# LED_MAT_HUB.net
KiCad netlist of a schematic drawn in Altium Designer
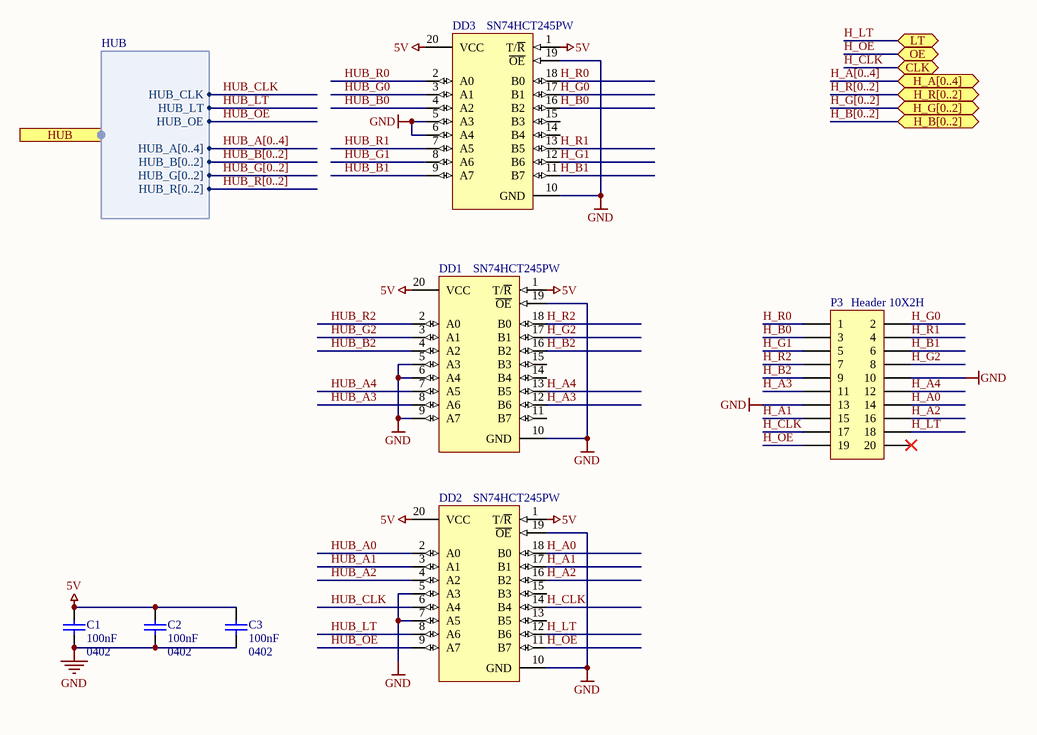
[diagram p0: LED_MAT_HUB.SchDoc]

(export (version "E")
  (design (tool "Eeschema 10.0.6"))
  (components
    (comp (ref "C1")
      (value "100nF")
      (footprint "CAPC1005L")
      (description "Capacitor ceramic")
      (fields
        (field (name "MANUFACTURER") "SAMSUNG")
        (field (name "MANUFACTURER PART NUMBER") "CL05B104KO5NNNC")
        (field (name "PACKAGE") "0402")
      )
      (libsource (lib "LED_MAT_3") (part "100nF / 0402 / X7R / 16V"))
    )
    (comp (ref "C2")
      (value "100nF")
      (footprint "CAPC1005L")
      (description "Capacitor ceramic")
      (fields
        (field (name "MANUFACTURER") "SAMSUNG")
        (field (name "MANUFACTURER PART NUMBER") "CL05B104KO5NNNC")
        (field (name "PACKAGE") "0402")
      )
      (libsource (lib "LED_MAT_3") (part "100nF / 0402 / X7R / 16V"))
    )
    (comp (ref "C3")
      (value "100nF")
      (footprint "CAPC1005L")
      (description "Capacitor ceramic")
      (fields
        (field (name "MANUFACTURER") "SAMSUNG")
        (field (name "MANUFACTURER PART NUMBER") "CL05B104KO5NNNC")
        (field (name "PACKAGE") "0402")
      )
      (libsource (lib "LED_MAT_3") (part "100nF / 0402 / X7R / 16V"))
    )
    (comp (ref "DD1")
      (value "SN74HCT245PW")
      (footprint "PW020_N")
      (description "Octal 3-State Noninverting Bus Transceiver")
      (fields
        (field (name "MANUFACTURER") "NEXPERIA")
        (field (name "MANUFACTURER PART NUMBER") "SN74HCT245PW")
      )
      (libsource (lib "LED_MAT_3") (part "SN74HCT245PW"))
    )
    (comp (ref "DD2")
      (value "SN74HCT245PW")
      (footprint "PW020_N")
      (description "Octal 3-State Noninverting Bus Transceiver")
      (fields
        (field (name "MANUFACTURER") "NEXPERIA")
        (field (name "MANUFACTURER PART NUMBER") "SN74HCT245PW")
      )
      (libsource (lib "LED_MAT_3") (part "SN74HCT245PW"))
    )
    (comp (ref "DD3")
      (value "SN74HCT245PW")
      (footprint "PW020_N")
      (description "Octal 3-State Noninverting Bus Transceiver")
      (fields
        (field (name "MANUFACTURER") "NEXPERIA")
        (field (name "MANUFACTURER PART NUMBER") "SN74HCT245PW")
      )
      (libsource (lib "LED_MAT_3") (part "SN74HCT245PW"))
    )
    (comp (ref "P3")
      (value "Header 10X2H")
      (footprint "HDR2X10H")
      (description "Header, 10-Pin, Dual row, Right Angle")
      (libsource (lib "LED_MAT_3") (part "Header 10X2H"))
    )
  )
  (nets
    (net (code "2") (name "/HUB_A0") (class "Default")
      (node (ref "DD2") (pin "2") (pinfunction "A0_2") (pintype "bidirectional"))
    )
    (net (code "3") (name "/HUB_A1") (class "Default")
      (node (ref "DD2") (pin "3") (pinfunction "A1_3") (pintype "bidirectional"))
    )
    (net (code "4") (name "/HUB_A2") (class "Default")
      (node (ref "DD2") (pin "4") (pinfunction "A2_4") (pintype "bidirectional"))
    )
    (net (code "5") (name "/HUB_A3") (class "Default")
      (node (ref "DD1") (pin "8") (pinfunction "A6_8") (pintype "bidirectional"))
    )
    (net (code "6") (name "/HUB_A4") (class "Default")
      (node (ref "DD1") (pin "7") (pinfunction "A5_7") (pintype "bidirectional"))
    )
    (net (code "7") (name "/HUB_B0") (class "Default")
      (node (ref "DD3") (pin "4") (pinfunction "A2_4") (pintype "bidirectional"))
    )
    (net (code "8") (name "/HUB_B1") (class "Default")
      (node (ref "DD3") (pin "9") (pinfunction "A7_9") (pintype "bidirectional"))
    )
    (net (code "9") (name "/HUB_B2") (class "Default")
      (node (ref "DD1") (pin "4") (pinfunction "A2_4") (pintype "bidirectional"))
    )
    (net (code "11") (name "/HUB_CLK") (class "Default")
      (node (ref "DD2") (pin "6") (pinfunction "A4_6") (pintype "bidirectional"))
    )
    (net (code "12") (name "/HUB_G0") (class "Default")
      (node (ref "DD3") (pin "3") (pinfunction "A1_3") (pintype "bidirectional"))
    )
    (net (code "13") (name "/HUB_G1") (class "Default")
      (node (ref "DD3") (pin "8") (pinfunction "A6_8") (pintype "bidirectional"))
    )
    (net (code "14") (name "/HUB_G2") (class "Default")
      (node (ref "DD1") (pin "3") (pinfunction "A1_3") (pintype "bidirectional"))
    )
    (net (code "16") (name "/HUB_LT") (class "Default")
      (node (ref "DD2") (pin "8") (pinfunction "A6_8") (pintype "bidirectional"))
    )
    (net (code "17") (name "/HUB_OE") (class "Default")
      (node (ref "DD2") (pin "9") (pinfunction "A7_9") (pintype "bidirectional"))
    )
    (net (code "18") (name "/HUB_R0") (class "Default")
      (node (ref "DD3") (pin "2") (pinfunction "A0_2") (pintype "bidirectional"))
    )
    (net (code "19") (name "/HUB_R1") (class "Default")
      (node (ref "DD3") (pin "7") (pinfunction "A5_7") (pintype "bidirectional"))
    )
    (net (code "20") (name "/HUB_R2") (class "Default")
      (node (ref "DD1") (pin "2") (pinfunction "A0_2") (pintype "bidirectional"))
    )
    (net (code "23") (name "/H_A0") (class "Default")
      (node (ref "DD2") (pin "18") (pinfunction "B0_18") (pintype "bidirectional"))
      (node (ref "P3") (pin "14") (pinfunction "14_14") (pintype "passive"))
    )
    (net (code "24") (name "/H_A1") (class "Default")
      (node (ref "DD2") (pin "17") (pinfunction "B1_17") (pintype "bidirectional"))
      (node (ref "P3") (pin "15") (pinfunction "15_15") (pintype "passive"))
    )
    (net (code "25") (name "/H_A2") (class "Default")
      (node (ref "DD2") (pin "16") (pinfunction "B2_16") (pintype "bidirectional"))
      (node (ref "P3") (pin "16") (pinfunction "16_16") (pintype "passive"))
    )
    (net (code "26") (name "/H_A3") (class "Default")
      (node (ref "DD1") (pin "12") (pinfunction "B6_12") (pintype "bidirectional"))
      (node (ref "P3") (pin "11") (pinfunction "11_11") (pintype "passive"))
    )
    (net (code "27") (name "/H_A4") (class "Default")
      (node (ref "DD1") (pin "13") (pinfunction "B5_13") (pintype "bidirectional"))
      (node (ref "P3") (pin "12") (pinfunction "12_12") (pintype "passive"))
    )
    (net (code "29") (name "/H_B0") (class "Default")
      (node (ref "DD3") (pin "16") (pinfunction "B2_16") (pintype "bidirectional"))
      (node (ref "P3") (pin "3") (pinfunction "3_3") (pintype "passive"))
    )
    (net (code "30") (name "/H_B1") (class "Default")
      (node (ref "DD3") (pin "11") (pinfunction "B7_11") (pintype "bidirectional"))
      (node (ref "P3") (pin "6") (pinfunction "6_6") (pintype "passive"))
    )
    (net (code "31") (name "/H_B2") (class "Default")
      (node (ref "DD1") (pin "16") (pinfunction "B2_16") (pintype "bidirectional"))
      (node (ref "P3") (pin "9") (pinfunction "9_9") (pintype "passive"))
    )
    (net (code "33") (name "/H_CLK") (class "Default")
      (node (ref "DD2") (pin "14") (pinfunction "B4_14") (pintype "bidirectional"))
      (node (ref "P3") (pin "17") (pinfunction "17_17") (pintype "passive"))
    )
    (net (code "34") (name "/H_G0") (class "Default")
      (node (ref "DD3") (pin "17") (pinfunction "B1_17") (pintype "bidirectional"))
      (node (ref "P3") (pin "2") (pinfunction "2_2") (pintype "passive"))
    )
    (net (code "35") (name "/H_G1") (class "Default")
      (node (ref "DD3") (pin "12") (pinfunction "B6_12") (pintype "bidirectional"))
      (node (ref "P3") (pin "5") (pinfunction "5_5") (pintype "passive"))
    )
    (net (code "36") (name "/H_G2") (class "Default")
      (node (ref "DD1") (pin "17") (pinfunction "B1_17") (pintype "bidirectional"))
      (node (ref "P3") (pin "8") (pinfunction "8_8") (pintype "passive"))
    )
    (net (code "38") (name "/H_LT") (class "Default")
      (node (ref "DD2") (pin "12") (pinfunction "B6_12") (pintype "bidirectional"))
      (node (ref "P3") (pin "18") (pinfunction "18_18") (pintype "passive"))
    )
    (net (code "39") (name "/H_OE") (class "Default")
      (node (ref "DD2") (pin "11") (pinfunction "B7_11") (pintype "bidirectional"))
      (node (ref "P3") (pin "19") (pinfunction "19_19") (pintype "passive"))
    )
    (net (code "40") (name "/H_R0") (class "Default")
      (node (ref "DD3") (pin "18") (pinfunction "B0_18") (pintype "bidirectional"))
      (node (ref "P3") (pin "1") (pinfunction "1_1") (pintype "passive"))
    )
    (net (code "41") (name "/H_R1") (class "Default")
      (node (ref "DD3") (pin "13") (pinfunction "B5_13") (pintype "bidirectional"))
      (node (ref "P3") (pin "4") (pinfunction "4_4") (pintype "passive"))
    )
    (net (code "42") (name "/H_R2") (class "Default")
      (node (ref "DD1") (pin "18") (pinfunction "B0_18") (pintype "bidirectional"))
      (node (ref "P3") (pin "7") (pinfunction "7_7") (pintype "passive"))
    )
    (net (code "44") (name "5V") (class "Default")
      (node (ref "C1") (pin "2") (pinfunction "2_2") (pintype "passive"))
      (node (ref "C2") (pin "2") (pinfunction "2_2") (pintype "passive"))
      (node (ref "C3") (pin "2") (pinfunction "2_2") (pintype "passive"))
      (node (ref "DD1") (pin "1") (pinfunction "T/~{R}_1") (pintype "input"))
      (node (ref "DD1") (pin "20") (pinfunction "VCC_20") (pintype "power_in"))
      (node (ref "DD2") (pin "1") (pinfunction "T/~{R}_1") (pintype "input"))
      (node (ref "DD2") (pin "20") (pinfunction "VCC_20") (pintype "power_in"))
      (node (ref "DD3") (pin "1") (pinfunction "T/~{R}_1") (pintype "input"))
      (node (ref "DD3") (pin "20") (pinfunction "VCC_20") (pintype "power_in"))
    )
    (net (code "45") (name "GND") (class "Default")
      (node (ref "C1") (pin "1") (pinfunction "1_1") (pintype "passive"))
      (node (ref "C2") (pin "1") (pinfunction "1_1") (pintype "passive"))
      (node (ref "C3") (pin "1") (pinfunction "1_1") (pintype "passive"))
      (node (ref "DD1") (pin "10") (pinfunction "GND_10") (pintype "power_in"))
      (node (ref "DD1") (pin "19") (pinfunction "~{OE}_19") (pintype "input"))
      (node (ref "DD1") (pin "5") (pinfunction "A3_5") (pintype "bidirectional"))
      (node (ref "DD1") (pin "6") (pinfunction "A4_6") (pintype "bidirectional"))
      (node (ref "DD1") (pin "9") (pinfunction "A7_9") (pintype "bidirectional"))
      (node (ref "DD2") (pin "10") (pinfunction "GND_10") (pintype "power_in"))
      (node (ref "DD2") (pin "19") (pinfunction "~{OE}_19") (pintype "input"))
      (node (ref "DD2") (pin "5") (pinfunction "A3_5") (pintype "bidirectional"))
      (node (ref "DD2") (pin "7") (pinfunction "A5_7") (pintype "bidirectional"))
      (node (ref "DD3") (pin "10") (pinfunction "GND_10") (pintype "power_in"))
      (node (ref "DD3") (pin "19") (pinfunction "~{OE}_19") (pintype "input"))
      (node (ref "DD3") (pin "5") (pinfunction "A3_5") (pintype "bidirectional"))
      (node (ref "DD3") (pin "6") (pinfunction "A4_6") (pintype "bidirectional"))
      (node (ref "P3") (pin "10") (pinfunction "10_10") (pintype "passive"))
      (node (ref "P3") (pin "13") (pinfunction "13_13") (pintype "passive"))
    )
    (net (code "46") (name "unconnected-(DD1-B3-Pad15)") (class "Default")
      (node (ref "DD1") (pin "15") (pinfunction "B3_15") (pintype "bidirectional"))
    )
    (net (code "47") (name "unconnected-(DD1-B4-Pad14)") (class "Default")
      (node (ref "DD1") (pin "14") (pinfunction "B4_14") (pintype "bidirectional"))
    )
    (net (code "48") (name "unconnected-(DD1-B7-Pad11)") (class "Default")
      (node (ref "DD1") (pin "11") (pinfunction "B7_11") (pintype "bidirectional"))
    )
    (net (code "49") (name "unconnected-(DD2-B3-Pad15)") (class "Default")
      (node (ref "DD2") (pin "15") (pinfunction "B3_15") (pintype "bidirectional"))
    )
    (net (code "50") (name "unconnected-(DD2-B5-Pad13)") (class "Default")
      (node (ref "DD2") (pin "13") (pinfunction "B5_13") (pintype "bidirectional"))
    )
    (net (code "51") (name "unconnected-(DD3-B3-Pad15)") (class "Default")
      (node (ref "DD3") (pin "15") (pinfunction "B3_15") (pintype "bidirectional"))
    )
    (net (code "52") (name "unconnected-(DD3-B4-Pad14)") (class "Default")
      (node (ref "DD3") (pin "14") (pinfunction "B4_14") (pintype "bidirectional"))
    )
    (net (code "53") (name "unconnected-(P3-Pad20)") (class "Default")
      (node (ref "P3") (pin "20") (pinfunction "20_20") (pintype "passive+no_connect"))
    )
  )
)
